# MirZ21_Sub-D_Renamed_U.net
KiCad netlist of a schematic drawn in EAGLE
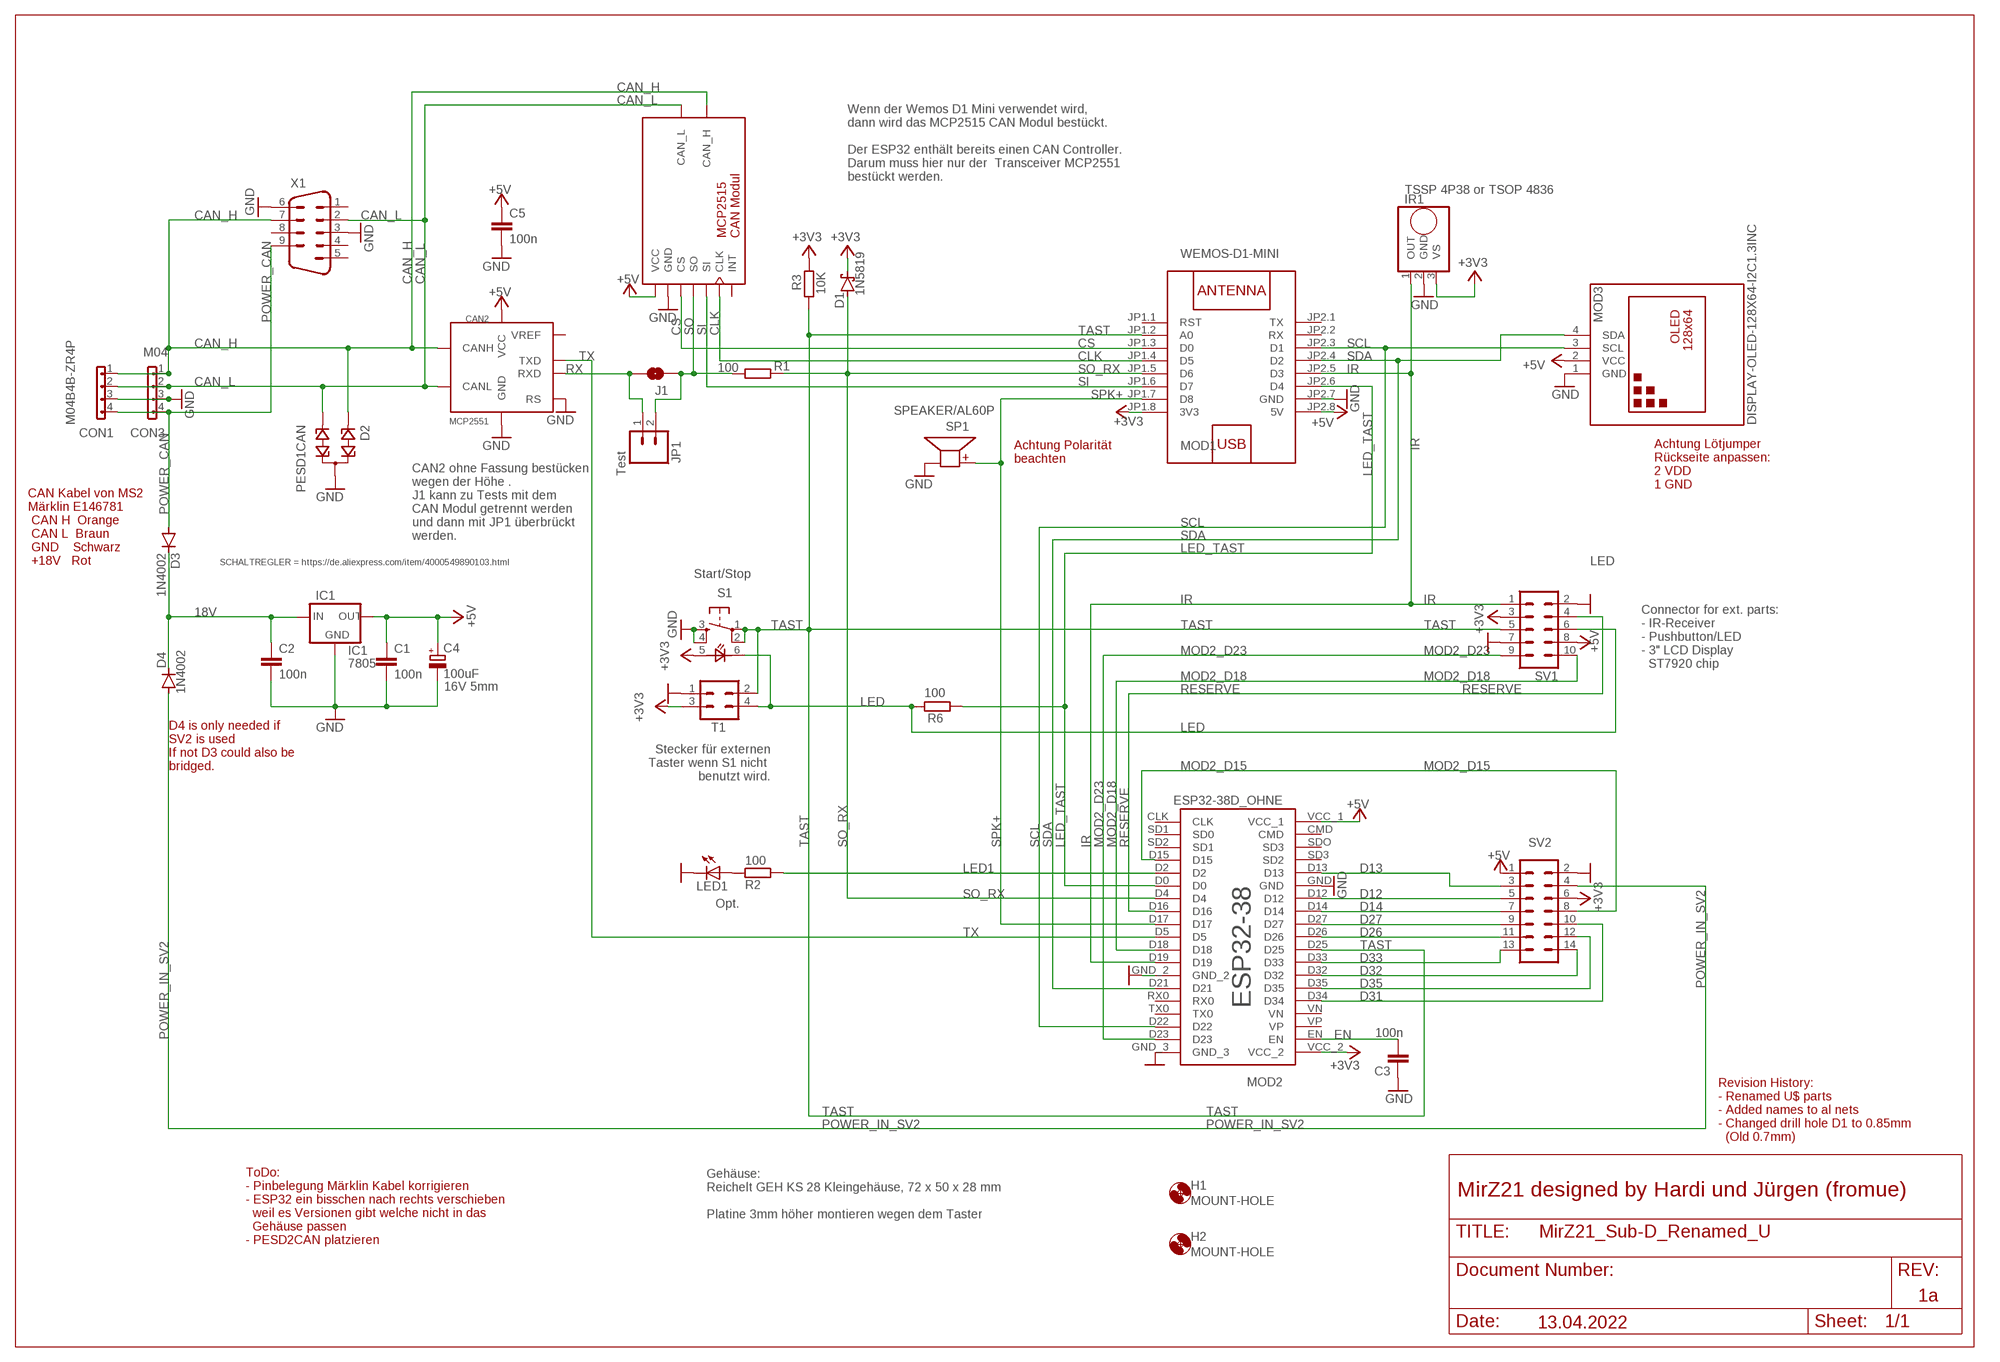
[diagram p0: schematic, sheet 1]

(export (version "E")
  (design (tool "Eeschema 10.0.6"))
  (components
    (comp (ref "C1")
      (value "100n")
      (footprint "eagle-import:C025-025X050")
      (libsource (lib "eagle-import") (part "C-EU025-025X050"))
    )
    (comp (ref "C2")
      (value "100n")
      (footprint "eagle-import:C025-025X050")
      (libsource (lib "eagle-import") (part "C-EU025-025X050"))
    )
    (comp (ref "C3")
      (value "100n")
      (footprint "eagle-import:C025-025X050")
      (libsource (lib "eagle-import") (part "C-EU025-025X050"))
    )
    (comp (ref "C4")
      (value "100uF")
      (footprint "eagle-import:TT2D5L")
      (fields (field (name "ADD") "16V 5mm"))
      (libsource (lib "eagle-import") (part "CPOL-EUTT2D5L"))
    )
    (comp (ref "C5")
      (value "100n")
      (footprint "eagle-import:C025-025X050")
      (libsource (lib "eagle-import") (part "C-EU025-025X050"))
    )
    (comp (ref "CAN1")
      (value "MCP2515_CAN_CUTCUT")
      (footprint "eagle-import:MCP2515_CAN_CUT")
      (libsource (lib "eagle-import") (part "MCP2515_CAN_CUTCUT"))
    )
    (comp (ref "CAN2")
      (value "MCP2551")
      (footprint "eagle-import:DIP08")
      (libsource (lib "eagle-import") (part "MCP2551DIP"))
    )
    (comp (ref "CON1")
      (value "M04B4B-ZR4P")
      (footprint "eagle-import:B4B-ZR4P")
      (libsource (lib "eagle-import") (part "M04B4B-ZR4P"))
    )
    (comp (ref "CON3")
      (value "M04")
      (footprint "eagle-import:1X04")
      (libsource (lib "eagle-import") (part "M04"))
    )
    (comp (ref "D1")
      (value "1N5819")
      (footprint "eagle-import:DO41-7.6")
      (libsource (lib "eagle-import") (part "1N581"))
    )
    (comp (ref "D2")
      (value "PESD1CAN")
      (footprint "eagle-import:SOT23")
      (libsource (lib "eagle-import") (part "PESD1CAN"))
    )
    (comp (ref "D3")
      (value "1N4002")
      (footprint "eagle-import:DO41-10")
      (libsource (lib "eagle-import") (part "1N4004"))
    )
    (comp (ref "D4")
      (value "1N4002")
      (footprint "eagle-import:DO41-10")
      (libsource (lib "eagle-import") (part "1N4004"))
    )
    (comp (ref "H1")
      (value "MOUNT-HOLE")
      (footprint "eagle-import:GEH_KS")
      (libsource (lib "eagle-import") (part "MOUNT-HOLE"))
    )
    (comp (ref "H2")
      (value "MOUNT-HOLE")
      (footprint "eagle-import:GEH_KS")
      (libsource (lib "eagle-import") (part "MOUNT-HOLE"))
    )
    (comp (ref "IC1")
      (value "7805")
      (footprint "eagle-import:HX1314G")
      (fields (field (name "SCHALTREGLER") "https://de.aliexpress.com/item/4000549890103.html"))
      (libsource (lib "eagle-import") (part "78XXSSTEPDOWN"))
    )
    (comp (ref "IR1")
      (value "TSSP 4P38 or TSOP 4836")
      (footprint "eagle-import:TSSP4P38")
      (libsource (lib "eagle-import") (part "TSSP4P38"))
    )
    (comp (ref "J1")
      (value "SOLDERJUMPERTRACE")
      (footprint "eagle-import:SJ_2S-TRACE")
      (libsource (lib "eagle-import") (part "SOLDERJUMPERTRACE"))
    )
    (comp (ref "JP1")
      (value "Test")
      (footprint "eagle-import:1X02")
      (libsource (lib "eagle-import") (part "M02PTH"))
    )
    (comp (ref "LED1")
      (value "Opt.")
      (footprint "eagle-import:LED3MM")
      (libsource (lib "eagle-import") (part "LED3MM"))
    )
    (comp (ref "MOD1")
      (value "WEMOS-D1-MINI")
      (footprint "eagle-import:WEMOS-D1-MINI")
      (libsource (lib "eagle-import") (part "WEMOS-D1-MINI"))
    )
    (comp (ref "MOD2")
      (value "ESP32-38D_OHNE")
      (footprint "eagle-import:ESP32-38D_0")
      (libsource (lib "eagle-import") (part "ESP32-38D_OHNE"))
    )
    (comp (ref "MOD3")
      (value "DISPLAY-OLED-128X64-I2C1.3INC")
      (footprint "eagle-import:DISPLAY-OLED-128X64-I2C-1.3")
      (libsource (lib "eagle-import") (part "DISPLAY-OLED-128X64-I2C1.3INC"))
    )
    (comp (ref "R1")
      (value "100")
      (footprint "eagle-import:0204_7")
      (libsource (lib "eagle-import") (part "R0204/7"))
    )
    (comp (ref "R2")
      (value "100")
      (footprint "eagle-import:0207_2V")
      (libsource (lib "eagle-import") (part "R-EU_0207/2V"))
    )
    (comp (ref "R3")
      (value "10K")
      (footprint "eagle-import:0204_7")
      (libsource (lib "eagle-import") (part "R0204/7"))
    )
    (comp (ref "R6")
      (value "100")
      (footprint "eagle-import:0204_7")
      (libsource (lib "eagle-import") (part "R0204/7"))
    )
    (comp (ref "S1")
      (value "TASTER_LEDTC-1198-B")
      (footprint "eagle-import:TASTER_LED")
      (libsource (lib "eagle-import") (part "TASTER_LEDTC-1198-B"))
    )
    (comp (ref "SP1")
      (value "SPEAKER/AL60P")
      (footprint "eagle-import:RMP-14SP")
      (libsource (lib "eagle-import") (part "SPEAKER/AL60P"))
    )
    (comp (ref "SV1")
      (value "ML10")
      (footprint "eagle-import:ML10")
      (libsource (lib "eagle-import") (part "ML10"))
    )
    (comp (ref "SV2")
      (value "ML14")
      (footprint "eagle-import:ML14")
      (libsource (lib "eagle-import") (part "ML14"))
    )
    (comp (ref "T1")
      (value "CON-HARTING-ML_ML4ML4_FEMALE")
      (footprint "eagle-import:ML_ML4_FEMALE")
      (libsource (lib "eagle-import") (part "CON-HARTING-ML_ML4ML4_FEMALE"))
    )
    (comp (ref "X1")
      (value "M09D")
      (footprint "eagle-import:M09D")
      (libsource (lib "eagle-import") (part "M09D"))
    )
  )
  (nets
    (net (code "1") (name "+3V3") (class "Default")
      (node (ref "D1") (pin "C") (pinfunction "C_C") (pintype "passive"))
      (node (ref "IR1") (pin "3") (pinfunction "VS_3") (pintype "power_in"))
      (node (ref "MOD1") (pin "JP1.8") (pinfunction "3V3_JP1.8") (pintype "power_in"))
      (node (ref "MOD2") (pin "VCC_2") (pinfunction "VCC_2_VCC_2") (pintype "power_in"))
      (node (ref "R3") (pin "2") (pinfunction "2_2") (pintype "passive"))
      (node (ref "S1") (pin "5") (pinfunction "+_5") (pintype "input"))
      (node (ref "SV1") (pin "3") (pinfunction "3_3") (pintype "passive"))
      (node (ref "SV2") (pin "6") (pinfunction "6_6") (pintype "passive"))
      (node (ref "T1") (pin "3") (pinfunction "3_3") (pintype "passive"))
    )
    (net (code "2") (name "+5V") (class "Default")
      (node (ref "C1") (pin "1") (pinfunction "1_1") (pintype "passive"))
      (node (ref "C4") (pin "+") (pinfunction "+_+") (pintype "passive"))
      (node (ref "C5") (pin "1") (pinfunction "1_1") (pintype "passive"))
      (node (ref "CAN1") (pin "1") (pinfunction "VCC_1") (pintype "power_in"))
      (node (ref "CAN2") (pin "3") (pinfunction "VCC_3") (pintype "power_in"))
      (node (ref "IC1") (pin "OUT") (pinfunction "OUT_OUT") (pintype "passive"))
      (node (ref "MOD1") (pin "JP2.8") (pinfunction "5V_JP2.8") (pintype "power_in"))
      (node (ref "MOD2") (pin "VCC_1") (pinfunction "VCC_1_VCC_1") (pintype "power_in"))
      (node (ref "MOD3") (pin "2") (pinfunction "VCC_2") (pintype "power_in"))
      (node (ref "SV1") (pin "8") (pinfunction "8_8") (pintype "passive"))
      (node (ref "SV2") (pin "1") (pinfunction "1_1") (pintype "passive"))
    )
    (net (code "3") (name "/18V") (class "Default")
      (node (ref "C2") (pin "1") (pinfunction "1_1") (pintype "passive"))
      (node (ref "D3") (pin "C") (pinfunction "C_C") (pintype "passive"))
      (node (ref "D4") (pin "C") (pinfunction "C_C") (pintype "passive"))
      (node (ref "IC1") (pin "IN") (pinfunction "IN_IN") (pintype "input"))
    )
    (net (code "4") (name "/CAN_H") (class "Default")
      (node (ref "CAN1") (pin "9") (pinfunction "CAN_H_9") (pintype "bidirectional"))
      (node (ref "CAN2") (pin "7") (pinfunction "CANH_7") (pintype "bidirectional"))
      (node (ref "CON1") (pin "1") (pinfunction "1_1") (pintype "passive"))
      (node (ref "CON3") (pin "1") (pinfunction "1_1") (pintype "passive"))
      (node (ref "D2") (pin "1") (pinfunction "1_1") (pintype "passive"))
      (node (ref "X1") (pin "7") (pinfunction "7_7") (pintype "passive"))
    )
    (net (code "5") (name "/CAN_L") (class "Default")
      (node (ref "CAN1") (pin "8") (pinfunction "CAN_L_8") (pintype "bidirectional"))
      (node (ref "CAN2") (pin "6") (pinfunction "CANL_6") (pintype "bidirectional"))
      (node (ref "CON1") (pin "2") (pinfunction "2_2") (pintype "passive"))
      (node (ref "CON3") (pin "2") (pinfunction "2_2") (pintype "passive"))
      (node (ref "D2") (pin "2") (pinfunction "2_2") (pintype "passive"))
      (node (ref "X1") (pin "2") (pinfunction "2_2") (pintype "passive"))
    )
    (net (code "6") (name "/CLK") (class "Default")
      (node (ref "CAN1") (pin "6") (pinfunction "CLK_6") (pintype "input"))
      (node (ref "MOD1") (pin "JP1.4") (pinfunction "D5_JP1.4") (pintype "bidirectional"))
    )
    (net (code "7") (name "/CS") (class "Default")
      (node (ref "CAN1") (pin "3") (pinfunction "CS_3") (pintype "input"))
      (node (ref "MOD1") (pin "JP1.3") (pinfunction "D0_JP1.3") (pintype "bidirectional"))
    )
    (net (code "8") (name "/D12") (class "Default")
      (node (ref "MOD2") (pin "D12") (pinfunction "D12_D12") (pintype "bidirectional"))
      (node (ref "SV2") (pin "5") (pinfunction "5_5") (pintype "passive"))
    )
    (net (code "9") (name "/D13") (class "Default")
      (node (ref "MOD2") (pin "D13") (pinfunction "D13_D13") (pintype "bidirectional"))
      (node (ref "SV2") (pin "3") (pinfunction "3_3") (pintype "passive"))
    )
    (net (code "10") (name "/D14") (class "Default")
      (node (ref "MOD2") (pin "D14") (pinfunction "D14_D14") (pintype "bidirectional"))
      (node (ref "SV2") (pin "7") (pinfunction "7_7") (pintype "passive"))
    )
    (net (code "11") (name "/D26") (class "Default")
      (node (ref "MOD2") (pin "D26") (pinfunction "D26_D26") (pintype "bidirectional"))
      (node (ref "SV2") (pin "11") (pinfunction "11_11") (pintype "passive"))
    )
    (net (code "12") (name "/D27") (class "Default")
      (node (ref "MOD2") (pin "D27") (pinfunction "D27_D27") (pintype "bidirectional"))
      (node (ref "SV2") (pin "9") (pinfunction "9_9") (pintype "passive"))
    )
    (net (code "13") (name "/D31") (class "Default")
      (node (ref "MOD2") (pin "D34") (pinfunction "D34_D34") (pintype "bidirectional"))
      (node (ref "SV2") (pin "10") (pinfunction "10_10") (pintype "passive"))
    )
    (net (code "14") (name "/D32") (class "Default")
      (node (ref "MOD2") (pin "D32") (pinfunction "D32_D32") (pintype "bidirectional"))
      (node (ref "SV2") (pin "14") (pinfunction "14_14") (pintype "passive"))
    )
    (net (code "15") (name "/D33") (class "Default")
      (node (ref "MOD2") (pin "D33") (pinfunction "D33_D33") (pintype "bidirectional"))
      (node (ref "SV2") (pin "13") (pinfunction "13_13") (pintype "passive"))
    )
    (net (code "16") (name "/D35") (class "Default")
      (node (ref "MOD2") (pin "D35") (pinfunction "D35_D35") (pintype "bidirectional"))
      (node (ref "SV2") (pin "12") (pinfunction "12_12") (pintype "passive"))
    )
    (net (code "17") (name "/EN") (class "Default")
      (node (ref "C3") (pin "2") (pinfunction "2_2") (pintype "passive"))
      (node (ref "MOD2") (pin "EN") (pinfunction "EN_EN") (pintype "input"))
    )
    (net (code "18") (name "/IR") (class "Default")
      (node (ref "IR1") (pin "1") (pinfunction "OUT_1") (pintype "output"))
      (node (ref "MOD1") (pin "JP2.5") (pinfunction "D3_JP2.5") (pintype "bidirectional"))
      (node (ref "MOD2") (pin "D19") (pinfunction "D19_D19") (pintype "bidirectional"))
      (node (ref "SV1") (pin "1") (pinfunction "1_1") (pintype "passive"))
    )
    (net (code "19") (name "/LED") (class "Default")
      (node (ref "R6") (pin "2") (pinfunction "2_2") (pintype "passive"))
      (node (ref "S1") (pin "6") (pinfunction "-_6") (pintype "input"))
      (node (ref "SV1") (pin "6") (pinfunction "6_6") (pintype "passive"))
      (node (ref "T1") (pin "4") (pinfunction "4_4") (pintype "passive"))
    )
    (net (code "20") (name "/LED1") (class "Default")
      (node (ref "MOD2") (pin "D2") (pinfunction "D2_D2") (pintype "bidirectional"))
      (node (ref "R2") (pin "2") (pinfunction "2_2") (pintype "passive"))
    )
    (net (code "21") (name "/LED_TAST") (class "Default")
      (node (ref "MOD1") (pin "JP2.6") (pinfunction "D4_JP2.6") (pintype "bidirectional"))
      (node (ref "MOD2") (pin "D0") (pinfunction "D0_D0") (pintype "input"))
      (node (ref "R6") (pin "1") (pinfunction "1_1") (pintype "passive"))
    )
    (net (code "22") (name "/MOD2_D15") (class "Default")
      (node (ref "MOD2") (pin "D15") (pinfunction "D15_D15") (pintype "bidirectional"))
      (node (ref "SV2") (pin "8") (pinfunction "8_8") (pintype "passive"))
    )
    (net (code "23") (name "/MOD2_D18") (class "Default")
      (node (ref "MOD2") (pin "D18") (pinfunction "D18_D18") (pintype "bidirectional"))
      (node (ref "SV1") (pin "10") (pinfunction "10_10") (pintype "passive"))
    )
    (net (code "24") (name "/MOD2_D23") (class "Default")
      (node (ref "MOD2") (pin "D23") (pinfunction "D23_D23") (pintype "bidirectional"))
      (node (ref "SV1") (pin "9") (pinfunction "9_9") (pintype "passive"))
    )
    (net (code "25") (name "/POWER_CAN") (class "Default")
      (node (ref "CON1") (pin "4") (pinfunction "4_4") (pintype "passive"))
      (node (ref "CON3") (pin "4") (pinfunction "4_4") (pintype "passive"))
      (node (ref "D3") (pin "A") (pinfunction "A_A") (pintype "passive"))
      (node (ref "X1") (pin "9") (pinfunction "9_9") (pintype "passive"))
    )
    (net (code "26") (name "/POWER_IN_SV2") (class "Default")
      (node (ref "D4") (pin "A") (pinfunction "A_A") (pintype "passive"))
      (node (ref "SV2") (pin "4") (pinfunction "4_4") (pintype "passive"))
    )
    (net (code "27") (name "/RESERVE") (class "Default")
      (node (ref "MOD2") (pin "D16") (pinfunction "D16_D16") (pintype "bidirectional"))
      (node (ref "SV1") (pin "4") (pinfunction "4_4") (pintype "passive"))
    )
    (net (code "28") (name "/RX") (class "Default")
      (node (ref "CAN2") (pin "4") (pinfunction "RXD_4") (pintype "power_in"))
      (node (ref "J1") (pin "2") (pinfunction "2_2") (pintype "passive"))
      (node (ref "JP1") (pin "1") (pinfunction "1_1") (pintype "passive"))
    )
    (net (code "29") (name "/SCL") (class "Default")
      (node (ref "MOD1") (pin "JP2.3") (pinfunction "D1_JP2.3") (pintype "bidirectional"))
      (node (ref "MOD2") (pin "D22") (pinfunction "D22_D22") (pintype "bidirectional"))
      (node (ref "MOD3") (pin "3") (pinfunction "SCL_3") (pintype "bidirectional"))
    )
    (net (code "30") (name "/SDA") (class "Default")
      (node (ref "MOD1") (pin "JP2.4") (pinfunction "D2_JP2.4") (pintype "bidirectional"))
      (node (ref "MOD2") (pin "D21") (pinfunction "D21_D21") (pintype "bidirectional"))
      (node (ref "MOD3") (pin "4") (pinfunction "SDA_4") (pintype "bidirectional"))
    )
    (net (code "31") (name "/SI") (class "Default")
      (node (ref "CAN1") (pin "5") (pinfunction "SI_5") (pintype "input"))
      (node (ref "MOD1") (pin "JP1.6") (pinfunction "D7_JP1.6") (pintype "bidirectional"))
    )
    (net (code "32") (name "/SO") (class "Default")
      (node (ref "CAN1") (pin "4") (pinfunction "SO_4") (pintype "output"))
      (node (ref "J1") (pin "1") (pinfunction "1_1") (pintype "passive"))
      (node (ref "JP1") (pin "2") (pinfunction "2_2") (pintype "passive"))
      (node (ref "R1") (pin "2") (pinfunction "2_2") (pintype "passive"))
    )
    (net (code "33") (name "/SO_RX") (class "Default")
      (node (ref "D1") (pin "A") (pinfunction "A_A") (pintype "passive"))
      (node (ref "MOD1") (pin "JP1.5") (pinfunction "D6_JP1.5") (pintype "bidirectional"))
      (node (ref "MOD2") (pin "D4") (pinfunction "D4_D4") (pintype "bidirectional"))
      (node (ref "R1") (pin "1") (pinfunction "1_1") (pintype "passive"))
    )
    (net (code "34") (name "/SPK+") (class "Default")
      (node (ref "MOD1") (pin "JP1.7") (pinfunction "D8_JP1.7") (pintype "bidirectional"))
      (node (ref "MOD2") (pin "D17") (pinfunction "D17_D17") (pintype "bidirectional"))
      (node (ref "SP1") (pin "1") (pinfunction "+_1") (pintype "passive"))
    )
    (net (code "35") (name "/TAST") (class "Default")
      (node (ref "MOD1") (pin "JP1.2") (pinfunction "A0_JP1.2") (pintype "bidirectional"))
      (node (ref "MOD2") (pin "D25") (pinfunction "D25_D25") (pintype "bidirectional"))
      (node (ref "R3") (pin "1") (pinfunction "1_1") (pintype "passive"))
      (node (ref "S1") (pin "1") (pinfunction "P_1") (pintype "passive"))
      (node (ref "S1") (pin "2") (pinfunction "P1_2") (pintype "passive"))
      (node (ref "SV1") (pin "5") (pinfunction "5_5") (pintype "passive"))
      (node (ref "T1") (pin "2") (pinfunction "2_2") (pintype "passive"))
    )
    (net (code "36") (name "/TX") (class "Default")
      (node (ref "CAN2") (pin "1") (pinfunction "TXD_1") (pintype "power_in"))
      (node (ref "MOD2") (pin "D5") (pinfunction "D5_D5") (pintype "bidirectional"))
    )
    (net (code "37") (name "/VREF") (class "Default")
      (node (ref "CAN2") (pin "5") (pinfunction "VREF_5") (pintype "power_in"))
    )
    (net (code "38") (name "GND") (class "Default")
      (node (ref "C1") (pin "2") (pinfunction "2_2") (pintype "passive"))
      (node (ref "C2") (pin "2") (pinfunction "2_2") (pintype "passive"))
      (node (ref "C3") (pin "1") (pinfunction "1_1") (pintype "passive"))
      (node (ref "C4") (pin "-") (pinfunction "-_-") (pintype "passive"))
      (node (ref "C5") (pin "2") (pinfunction "2_2") (pintype "passive"))
      (node (ref "CAN1") (pin "2") (pinfunction "GND_2") (pintype "power_in"))
      (node (ref "CAN2") (pin "2") (pinfunction "GND_2") (pintype "power_in"))
      (node (ref "CAN2") (pin "8") (pinfunction "RS_8") (pintype "power_in"))
      (node (ref "CON1") (pin "3") (pinfunction "3_3") (pintype "passive"))
      (node (ref "CON3") (pin "3") (pinfunction "3_3") (pintype "passive"))
      (node (ref "D2") (pin "3") (pinfunction "3_3") (pintype "passive"))
      (node (ref "IC1") (pin "GND") (pinfunction "GND_GND") (pintype "input"))
      (node (ref "IR1") (pin "2") (pinfunction "GND_2") (pintype "power_in"))
      (node (ref "LED1") (pin "K") (pinfunction "C_K") (pintype "passive"))
      (node (ref "MOD1") (pin "JP2.7") (pinfunction "GND_JP2.7") (pintype "power_in"))
      (node (ref "MOD2") (pin "GND") (pinfunction "GND_GND") (pintype "power_in"))
      (node (ref "MOD2") (pin "GND_2") (pinfunction "GND_2_GND_2") (pintype "power_in"))
      (node (ref "MOD2") (pin "GND_3") (pinfunction "GND_3_GND_3") (pintype "power_in"))
      (node (ref "MOD3") (pin "1") (pinfunction "GND_1") (pintype "power_in"))
      (node (ref "S1") (pin "3") (pinfunction "S_3") (pintype "passive"))
      (node (ref "S1") (pin "4") (pinfunction "S1_4") (pintype "passive"))
      (node (ref "SP1") (pin "2") (pinfunction "-_2") (pintype "passive"))
      (node (ref "SV1") (pin "2") (pinfunction "2_2") (pintype "passive"))
      (node (ref "SV1") (pin "7") (pinfunction "7_7") (pintype "passive"))
      (node (ref "SV2") (pin "2") (pinfunction "2_2") (pintype "passive"))
      (node (ref "T1") (pin "1") (pinfunction "1_1") (pintype "passive"))
      (node (ref "X1") (pin "3") (pinfunction "3_3") (pintype "passive"))
      (node (ref "X1") (pin "6") (pinfunction "6_6") (pintype "passive"))
    )
    (net (code "39") (name "Net-(LED1-PadA)") (class "Default")
      (node (ref "LED1") (pin "A") (pinfunction "A_A") (pintype "passive"))
      (node (ref "R2") (pin "1") (pinfunction "1_1") (pintype "passive"))
    )
    (net (code "40") (name "unconnected-(CAN1-INT-Pad7)") (class "Default")
      (node (ref "CAN1") (pin "7") (pinfunction "INT_7") (pintype "open_collector"))
    )
    (net (code "41") (name "unconnected-(MOD1-RST-PadJP1.1)") (class "Default")
      (node (ref "MOD1") (pin "JP1.1") (pinfunction "RST_JP1.1") (pintype "bidirectional"))
    )
    (net (code "42") (name "unconnected-(MOD1-RX-PadJP2.2)") (class "Default")
      (node (ref "MOD1") (pin "JP2.2") (pinfunction "RX_JP2.2") (pintype "bidirectional"))
    )
    (net (code "43") (name "unconnected-(MOD1-TX-PadJP2.1)") (class "Default")
      (node (ref "MOD1") (pin "JP2.1") (pinfunction "TX_JP2.1") (pintype "bidirectional"))
    )
    (net (code "44") (name "unconnected-(MOD2-PadCLK)") (class "Default")
      (node (ref "MOD2") (pin "CLK") (pinfunction "CLK_CLK") (pintype "no_connect"))
    )
    (net (code "45") (name "unconnected-(MOD2-PadCMD)") (class "Default")
      (node (ref "MOD2") (pin "CMD") (pinfunction "CMD_CMD") (pintype "no_connect"))
    )
    (net (code "46") (name "unconnected-(MOD2-PadRX0)") (class "Default")
      (node (ref "MOD2") (pin "RX0") (pinfunction "RX0_RX0") (pintype "bidirectional"))
    )
    (net (code "47") (name "unconnected-(MOD2-PadTX0)") (class "Default")
      (node (ref "MOD2") (pin "TX0") (pinfunction "TX0_TX0") (pintype "bidirectional"))
    )
    (net (code "48") (name "unconnected-(MOD2-PadVN)") (class "Default")
      (node (ref "MOD2") (pin "VN") (pinfunction "VN_VN") (pintype "bidirectional"))
    )
    (net (code "49") (name "unconnected-(MOD2-PadVP)") (class "Default")
      (node (ref "MOD2") (pin "VP") (pinfunction "VP_VP") (pintype "bidirectional"))
    )
    (net (code "50") (name "unconnected-(MOD2-SD0-PadSD1)") (class "Default")
      (node (ref "MOD2") (pin "SD1") (pinfunction "SD0_SD1") (pintype "no_connect"))
    )
    (net (code "51") (name "unconnected-(MOD2-SD1-PadSD2)") (class "Default")
      (node (ref "MOD2") (pin "SD2") (pinfunction "SD1_SD2") (pintype "no_connect"))
    )
    (net (code "52") (name "unconnected-(MOD2-SD2-PadSD3)") (class "Default")
      (node (ref "MOD2") (pin "SD3") (pinfunction "SD2_SD3") (pintype "no_connect"))
    )
    (net (code "53") (name "unconnected-(MOD2-SD3-PadSDO)") (class "Default")
      (node (ref "MOD2") (pin "SDO") (pinfunction "SD3_SDO") (pintype "no_connect"))
    )
    (net (code "54") (name "unconnected-(X1-Pad1)") (class "Default")
      (node (ref "X1") (pin "1") (pinfunction "1_1") (pintype "passive"))
    )
    (net (code "55") (name "unconnected-(X1-Pad4)") (class "Default")
      (node (ref "X1") (pin "4") (pinfunction "4_4") (pintype "passive"))
    )
    (net (code "56") (name "unconnected-(X1-Pad5)") (class "Default")
      (node (ref "X1") (pin "5") (pinfunction "5_5") (pintype "passive"))
    )
    (net (code "57") (name "unconnected-(X1-Pad8)") (class "Default")
      (node (ref "X1") (pin "8") (pinfunction "8_8") (pintype "passive"))
    )
  )
)
